# BOOST_CNTRL_CARD.net
KiCad netlist of a schematic drawn in Altium Designer
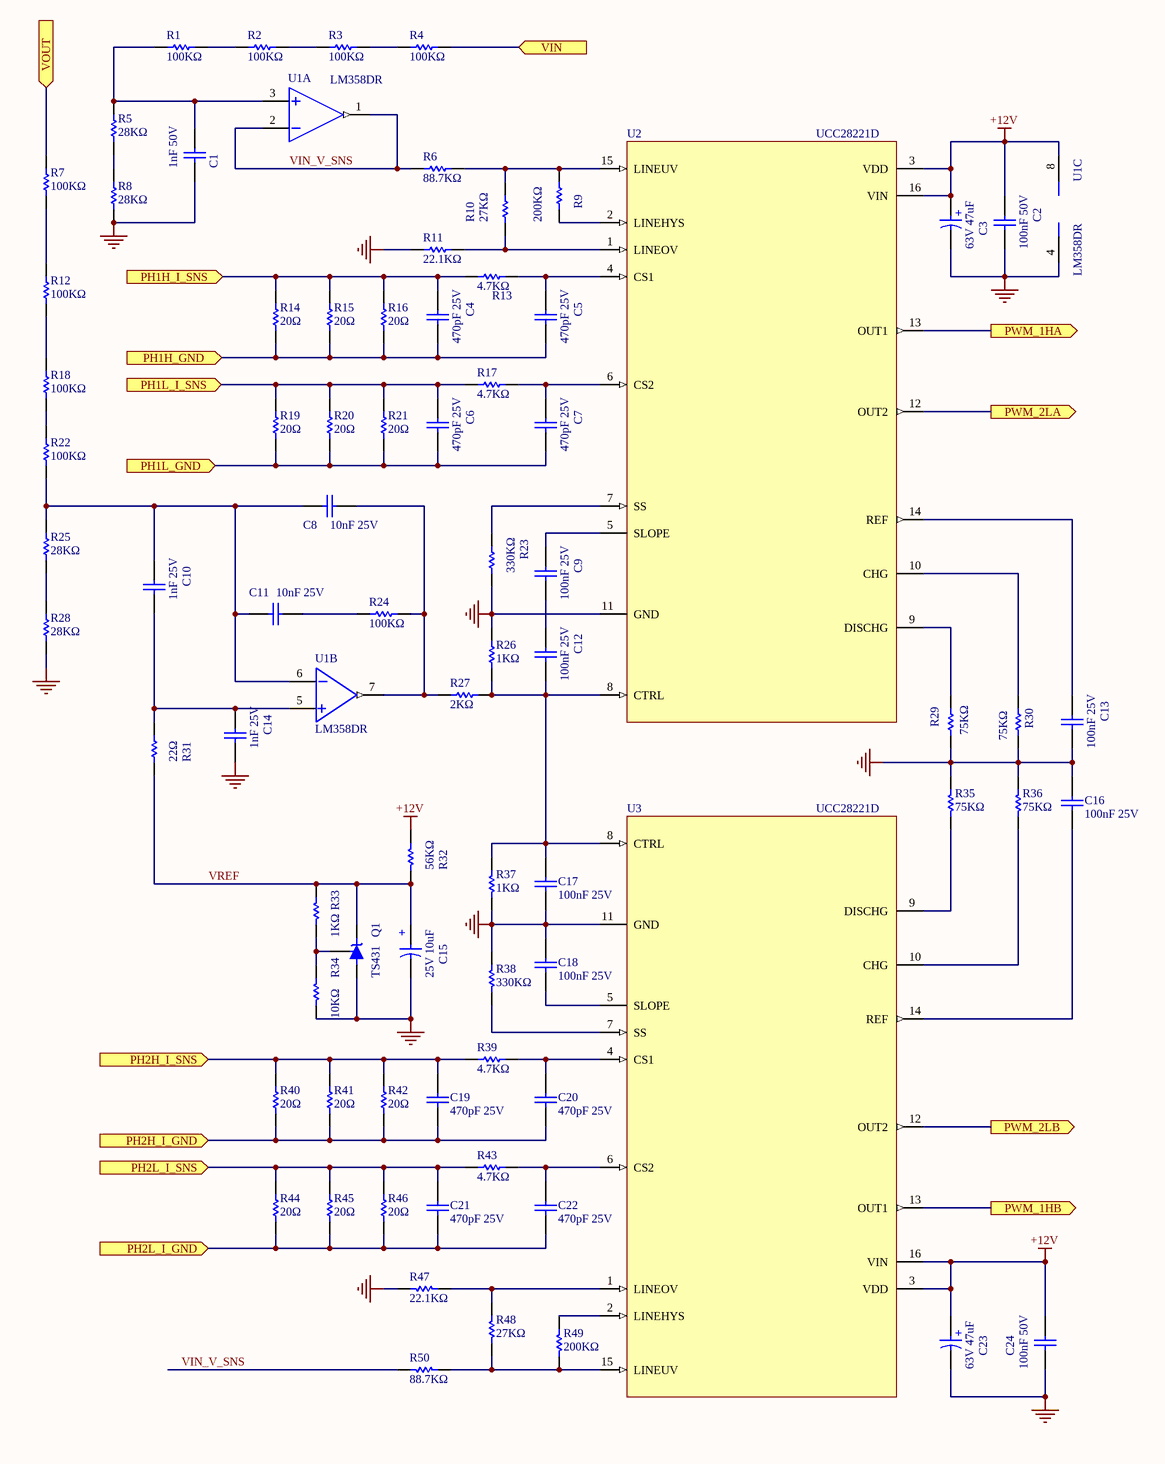
[diagram p0: BOOST CNTRL CARD.SchDoc]

(export (version "E")
  (design (tool "Eeschema 10.0.6"))
  (components
    (comp (ref "C1")
      (value "1nF 50V")
      (footprint "WCAP-CSGP_0402_L1W0.5H0.5")
      (description "WCAP-CSGP Multilayer Ceramic Chip Capacitor, General Purpose, size 0402, NP0, 1nF, 50VDC")
      (fields
        (field (name "MANUFACTURER PART NUMBER") "885012005067")
        (field (name "MANUFACTURER") "Wurth Elektronik")
      )
      (libsource (lib "WE - Passive Components") (part "Capacitor_Non-Polarized"))
    )
    (comp (ref "C2")
      (value "100nF 50V")
      (footprint "WCAP-CSGP_0805_L2W1.25H0.8_Reflow")
      (description "WCAP-CSGP Multilayer Ceramic Chip Capacitor, General Purpose, size 0805, X7R, 100nF, 50VDC")
      (fields
        (field (name "MANUFACTURER PART NUMBER") "885012207098")
        (field (name "MANUFACTURER") "Wurth Elektronik")
      )
      (libsource (lib "WE - Passive Components") (part "Capacitor_Non-Polarized"))
    )
    (comp (ref "C3")
      (value "63V 47uF")
      (footprint "WCAP-ASLI_D8H10.5")
      (description "WCAP-ASLI Aluminum Electrolytic Capacitor, V-Chip, D8 x H10.5mm, 47uF, 63V")
      (fields
        (field (name "MANUFACTURER PART NUMBER") "865080753013")
        (field (name "MANUFACTURER") "Wurth Elektronik")
      )
      (libsource (lib "WE - Passive Components") (part "Capacitor_Polarized"))
    )
    (comp (ref "C4")
      (value "470pF 25V")
      (footprint "WCAP-CSGP_0402_L1W0.5H0.5")
      (description "WCAP-CSGP Multilayer Ceramic Chip Capacitor, General Purpose, size 0402, X7R, 470pF, 25VDC")
      (fields
        (field (name "MANUFACTURER PART NUMBER") "885012205042")
        (field (name "MANUFACTURER") "Wurth Elektronik")
      )
      (libsource (lib "WE - Passive Components") (part "Capacitor_Non-Polarized"))
    )
    (comp (ref "C5")
      (value "470pF 25V")
      (footprint "WCAP-CSGP_0402_L1W0.5H0.5")
      (description "WCAP-CSGP Multilayer Ceramic Chip Capacitor, General Purpose, size 0402, X7R, 470pF, 25VDC")
      (fields
        (field (name "MANUFACTURER PART NUMBER") "885012205042")
        (field (name "MANUFACTURER") "Wurth Elektronik")
      )
      (libsource (lib "WE - Passive Components") (part "Capacitor_Non-Polarized"))
    )
    (comp (ref "C6")
      (value "470pF 25V")
      (footprint "WCAP-CSGP_0402_L1W0.5H0.5")
      (description "WCAP-CSGP Multilayer Ceramic Chip Capacitor, General Purpose, size 0402, X7R, 470pF, 25VDC")
      (fields
        (field (name "MANUFACTURER PART NUMBER") "885012205042")
        (field (name "MANUFACTURER") "Wurth Elektronik")
      )
      (libsource (lib "WE - Passive Components") (part "Capacitor_Non-Polarized"))
    )
    (comp (ref "C7")
      (value "470pF 25V")
      (footprint "WCAP-CSGP_0402_L1W0.5H0.5")
      (description "WCAP-CSGP Multilayer Ceramic Chip Capacitor, General Purpose, size 0402, X7R, 470pF, 25VDC")
      (fields
        (field (name "MANUFACTURER PART NUMBER") "885012205042")
        (field (name "MANUFACTURER") "Wurth Elektronik")
      )
      (libsource (lib "WE - Passive Components") (part "Capacitor_Non-Polarized"))
    )
    (comp (ref "C8")
      (value "10nF 25V")
      (footprint "WCAP-CSGP_0201_L0.6W0.3H0.3")
      (description "WCAP-CSGP Multilayer Ceramic Chip Capacitor, General Purpose, size 0201, X7R Class II, 10nF, 25VDC")
      (fields
        (field (name "MANUFACTURER PART NUMBER") "885012204004")
        (field (name "MANUFACTURER") "Wurth Elektronik")
      )
      (libsource (lib "WE - Passive Components") (part "Capacitor_Non-Polarized"))
    )
    (comp (ref "C9")
      (value "100nF 25V")
      (footprint "WCAP-CSGP_0402_L1W0.5H0.5")
      (description "WCAP-CSGP Multilayer Ceramic Chip Capacitor, General Purpose, size 0402, X7R, 100nF, 25VDC")
      (fields
        (field (name "MANUFACTURER PART NUMBER") "885012205085R")
        (field (name "MANUFACTURER") "Wurth Elektronik")
      )
      (libsource (lib "WE - Passive Components") (part "Capacitor_Non-Polarized"))
    )
    (comp (ref "C10")
      (value "1nF 25V")
      (footprint "WCAP-CSGP_0201_L0.6W0.3H0.3")
      (description "WCAP-CSGP Multilayer Ceramic Chip Capacitor, General Purpose, size 0201, X7R Class II, 1nF, 25VDC")
      (fields
        (field (name "MANUFACTURER PART NUMBER") "885012204006")
        (field (name "MANUFACTURER") "Wurth Elektronik")
      )
      (libsource (lib "WE - Passive Components") (part "Capacitor_Non-Polarized"))
    )
    (comp (ref "C11")
      (value "10nF 25V")
      (footprint "WCAP-CSGP_0201_L0.6W0.3H0.3")
      (description "WCAP-CSGP Multilayer Ceramic Chip Capacitor, General Purpose, size 0201, X7R Class II, 10nF, 25VDC")
      (fields
        (field (name "MANUFACTURER PART NUMBER") "885012204004")
        (field (name "MANUFACTURER") "Wurth Elektronik")
      )
      (libsource (lib "WE - Passive Components") (part "Capacitor_Non-Polarized"))
    )
    (comp (ref "C12")
      (value "100nF 25V")
      (footprint "WCAP-CSGP_0402_L1W0.5H0.5")
      (description "WCAP-CSGP Multilayer Ceramic Chip Capacitor, General Purpose, size 0402, X7R, 100nF, 25VDC")
      (fields
        (field (name "MANUFACTURER PART NUMBER") "885012205085R")
        (field (name "MANUFACTURER") "Wurth Elektronik")
      )
      (libsource (lib "WE - Passive Components") (part "Capacitor_Non-Polarized"))
    )
    (comp (ref "C13")
      (value "100nF 25V")
      (footprint "WCAP-CSGP_0402_L1W0.5H0.5")
      (description "WCAP-CSGP Multilayer Ceramic Chip Capacitor, General Purpose, size 0402, X7R, 100nF, 25VDC")
      (fields
        (field (name "MANUFACTURER PART NUMBER") "885012205085R")
        (field (name "MANUFACTURER") "Wurth Elektronik")
      )
      (libsource (lib "WE - Passive Components") (part "Capacitor_Non-Polarized"))
    )
    (comp (ref "C14")
      (value "1nF 25V")
      (footprint "WCAP-CSGP_0201_L0.6W0.3H0.3")
      (description "WCAP-CSGP Multilayer Ceramic Chip Capacitor, General Purpose, size 0201, X7R Class II, 1nF, 25VDC")
      (fields
        (field (name "MANUFACTURER PART NUMBER") "885012204006")
        (field (name "MANUFACTURER") "Wurth Elektronik")
      )
      (libsource (lib "WE - Passive Components") (part "Capacitor_Non-Polarized"))
    )
    (comp (ref "C15")
      (value "25V 10uF")
      (footprint "WCAP-AS5H_D4H5.5")
      (description "WCAP-AS5H Aluminum Electrolytic Capacitor, V-Chip, D4 x H5.5mm, 10µF, 25V")
      (fields
        (field (name "MANUFACTURER PART NUMBER") "865230440002")
        (field (name "MANUFACTURER") "Wurth Elektronik")
      )
      (libsource (lib "") (part "Capacitor_Polarized_1"))
    )
    (comp (ref "C16")
      (value "100nF 25V")
      (footprint "WCAP-CSGP_0402_L1W0.5H0.5")
      (description "WCAP-CSGP Multilayer Ceramic Chip Capacitor, General Purpose, size 0402, X7R, 100nF, 25VDC")
      (fields
        (field (name "MANUFACTURER PART NUMBER") "885012205085R")
        (field (name "MANUFACTURER") "Wurth Elektronik")
      )
      (libsource (lib "WE - Passive Components") (part "Capacitor_Non-Polarized"))
    )
    (comp (ref "C17")
      (value "100nF 25V")
      (footprint "WCAP-CSGP_0402_L1W0.5H0.5")
      (description "WCAP-CSGP Multilayer Ceramic Chip Capacitor, General Purpose, size 0402, X7R, 100nF, 25VDC")
      (fields
        (field (name "MANUFACTURER PART NUMBER") "885012205085R")
        (field (name "MANUFACTURER") "Wurth Elektronik")
      )
      (libsource (lib "WE - Passive Components") (part "Capacitor_Non-Polarized"))
    )
    (comp (ref "C18")
      (value "100nF 25V")
      (footprint "WCAP-CSGP_0402_L1W0.5H0.5")
      (description "WCAP-CSGP Multilayer Ceramic Chip Capacitor, General Purpose, size 0402, X7R, 100nF, 25VDC")
      (fields
        (field (name "MANUFACTURER PART NUMBER") "885012205085R")
        (field (name "MANUFACTURER") "Wurth Elektronik")
      )
      (libsource (lib "WE - Passive Components") (part "Capacitor_Non-Polarized"))
    )
    (comp (ref "C19")
      (value "470pF 25V")
      (footprint "WCAP-CSGP_0402_L1W0.5H0.5")
      (description "WCAP-CSGP Multilayer Ceramic Chip Capacitor, General Purpose, size 0402, X7R, 470pF, 25VDC")
      (fields
        (field (name "MANUFACTURER PART NUMBER") "885012205042")
        (field (name "MANUFACTURER") "Wurth Elektronik")
      )
      (libsource (lib "WE - Passive Components") (part "Capacitor_Non-Polarized"))
    )
    (comp (ref "C20")
      (value "470pF 25V")
      (footprint "WCAP-CSGP_0402_L1W0.5H0.5")
      (description "WCAP-CSGP Multilayer Ceramic Chip Capacitor, General Purpose, size 0402, X7R, 470pF, 25VDC")
      (fields
        (field (name "MANUFACTURER PART NUMBER") "885012205042")
        (field (name "MANUFACTURER") "Wurth Elektronik")
      )
      (libsource (lib "WE - Passive Components") (part "Capacitor_Non-Polarized"))
    )
    (comp (ref "C21")
      (value "470pF 25V")
      (footprint "WCAP-CSGP_0402_L1W0.5H0.5")
      (description "WCAP-CSGP Multilayer Ceramic Chip Capacitor, General Purpose, size 0402, X7R, 470pF, 25VDC")
      (fields
        (field (name "MANUFACTURER PART NUMBER") "885012205042")
        (field (name "MANUFACTURER") "Wurth Elektronik")
      )
      (libsource (lib "WE - Passive Components") (part "Capacitor_Non-Polarized"))
    )
    (comp (ref "C22")
      (value "470pF 25V")
      (footprint "WCAP-CSGP_0402_L1W0.5H0.5")
      (description "WCAP-CSGP Multilayer Ceramic Chip Capacitor, General Purpose, size 0402, X7R, 470pF, 25VDC")
      (fields
        (field (name "MANUFACTURER PART NUMBER") "885012205042")
        (field (name "MANUFACTURER") "Wurth Elektronik")
      )
      (libsource (lib "WE - Passive Components") (part "Capacitor_Non-Polarized"))
    )
    (comp (ref "C23")
      (value "63V 47uF")
      (footprint "WCAP-ASLI_D8H10.5")
      (description "WCAP-ASLI Aluminum Electrolytic Capacitor, V-Chip, D8 x H10.5mm, 47uF, 63V")
      (fields
        (field (name "MANUFACTURER PART NUMBER") "865080753013")
        (field (name "MANUFACTURER") "Wurth Elektronik")
      )
      (libsource (lib "WE - Passive Components") (part "Capacitor_Polarized"))
    )
    (comp (ref "C24")
      (value "100nF 50V")
      (footprint "WCAP-CSGP_0805_L2W1.25H0.8_Reflow")
      (description "WCAP-CSGP Multilayer Ceramic Chip Capacitor, General Purpose, size 0805, X7R, 100nF, 50VDC")
      (fields
        (field (name "MANUFACTURER PART NUMBER") "885012207098")
        (field (name "MANUFACTURER") "Wurth Elektronik")
      )
      (libsource (lib "WE - Passive Components") (part "Capacitor_Non-Polarized"))
    )
    (comp (ref "Q1")
      (value "TS431")
      (footprint "TO-92")
      (description "V-Ref Adjustable 1.24V to 6V 30mA 3-Pin TO-92 T/R")
      (fields
        (field (name "MANUFACTURER") "STMicroelectronics")
        (field (name "MANUFACTURER PART NUMBER") "TS431IZT")
      )
      (libsource (lib "Power Devices") (part "TS431IZT"))
    )
    (comp (ref "R1")
      (value "100KΩ")
      (footprint "WRIS-RSKS_0402")
      (description "WRIS-RSKS Thick Film Resistor, size 0402, 100000Ohm, 100mW")
      (fields
        (field (name "MANUFACTURER PART NUMBER") "560112110019")
        (field (name "MANUFACTURER") "Wurth Elektronik")
      )
      (libsource (lib "WE - Passive Components") (part "WRIS-RSKS"))
    )
    (comp (ref "R2")
      (value "100KΩ")
      (footprint "WRIS-RSKS_0402")
      (description "WRIS-RSKS Thick Film Resistor, size 0402, 100000Ohm, 100mW")
      (fields
        (field (name "MANUFACTURER PART NUMBER") "560112110019")
        (field (name "MANUFACTURER") "Wurth Elektronik")
      )
      (libsource (lib "WE - Passive Components") (part "WRIS-RSKS"))
    )
    (comp (ref "R3")
      (value "100KΩ")
      (footprint "WRIS-RSKS_0402")
      (description "WRIS-RSKS Thick Film Resistor, size 0402, 100000Ohm, 100mW")
      (fields
        (field (name "MANUFACTURER PART NUMBER") "560112110019")
        (field (name "MANUFACTURER") "Wurth Elektronik")
      )
      (libsource (lib "WE - Passive Components") (part "WRIS-RSKS"))
    )
    (comp (ref "R4")
      (value "100KΩ")
      (footprint "WRIS-RSKS_0402")
      (description "WRIS-RSKS Thick Film Resistor, size 0402, 100000Ohm, 100mW")
      (fields
        (field (name "MANUFACTURER PART NUMBER") "560112110019")
        (field (name "MANUFACTURER") "Wurth Elektronik")
      )
      (libsource (lib "WE - Passive Components") (part "WRIS-RSKS"))
    )
    (comp (ref "R5")
      (value "28KΩ")
      (footprint "WRIS-RSKS_0402")
      (description "WRIS-RSKS Thick Film Resistor, size 0402, 28000Ohm, 100mW")
      (fields
        (field (name "MANUFACTURER PART NUMBER") "560112110228")
        (field (name "MANUFACTURER") "Wurth Elektronik")
      )
      (libsource (lib "WE - Passive Components") (part "WRIS-RSKS"))
    )
    (comp (ref "R6")
      (value "88.7KΩ")
      (footprint "WRIS-RSKS_0402")
      (description "WRIS-RSKS Thick Film Resistor, size 0402, 88700Ohm, 100mW")
      (fields
        (field (name "MANUFACTURER PART NUMBER") "560112110139")
        (field (name "MANUFACTURER") "Wurth Elektronik")
      )
      (libsource (lib "WE - Passive Components") (part "WRIS-RSKS"))
    )
    (comp (ref "R7")
      (value "100KΩ")
      (footprint "WRIS-RSKS_0402")
      (description "WRIS-RSKS Thick Film Resistor, size 0402, 100000Ohm, 100mW")
      (fields
        (field (name "MANUFACTURER PART NUMBER") "560112110019")
        (field (name "MANUFACTURER") "Wurth Elektronik")
      )
      (libsource (lib "WE - Passive Components") (part "WRIS-RSKS"))
    )
    (comp (ref "R8")
      (value "28KΩ")
      (footprint "WRIS-RSKS_0402")
      (description "WRIS-RSKS Thick Film Resistor, size 0402, 28000Ohm, 100mW")
      (fields
        (field (name "MANUFACTURER PART NUMBER") "560112110228")
        (field (name "MANUFACTURER") "Wurth Elektronik")
      )
      (libsource (lib "WE - Passive Components") (part "WRIS-RSKS"))
    )
    (comp (ref "R9")
      (value "200KΩ")
      (footprint "WRIS-RSKS_0402")
      (description "WRIS-RSKS Thick Film Resistor, size 0402, 200000Ohm, 100mW")
      (fields
        (field (name "MANUFACTURER PART NUMBER") "560112110041")
        (field (name "MANUFACTURER") "Wurth Elektronik")
      )
      (libsource (lib "WE - Passive Components") (part "WRIS-RSKS"))
    )
    (comp (ref "R10")
      (value "27KΩ")
      (footprint "WRIS-RSKS_0402")
      (description "WRIS-RSKS Thick Film Resistor, size 0402, 27000Ohm, 100mW")
      (fields
        (field (name "MANUFACTURER PART NUMBER") "560112110026")
        (field (name "MANUFACTURER") "Wurth Elektronik")
      )
      (libsource (lib "WE - Passive Components") (part "WRIS-RSKS"))
    )
    (comp (ref "R11")
      (value "22.1KΩ")
      (footprint "WRIS-RSKS_0402")
      (description "WRIS-RSKS Thick Film Resistor, size 0402, 22100Ohm, 100mW")
      (fields
        (field (name "MANUFACTURER PART NUMBER") "560112110099")
        (field (name "MANUFACTURER") "Wurth Elektronik")
      )
      (libsource (lib "WE - Passive Components") (part "WRIS-RSKS"))
    )
    (comp (ref "R12")
      (value "100KΩ")
      (footprint "WRIS-RSKS_0402")
      (description "WRIS-RSKS Thick Film Resistor, size 0402, 100000Ohm, 100mW")
      (fields
        (field (name "MANUFACTURER PART NUMBER") "560112110019")
        (field (name "MANUFACTURER") "Wurth Elektronik")
      )
      (libsource (lib "WE - Passive Components") (part "WRIS-RSKS"))
    )
    (comp (ref "R13")
      (value "4.7KΩ")
      (footprint "WRIS-RSKS_0402")
      (description "WRIS-RSKS Thick Film Resistor, size 0402, 4700Ohm, 100mW")
      (fields
        (field (name "MANUFACTURER PART NUMBER") "560112110018")
        (field (name "MANUFACTURER") "Wurth Elektronik")
      )
      (libsource (lib "WE - Passive Components") (part "WRIS-RSKS"))
    )
    (comp (ref "R14")
      (value "20Ω")
      (footprint "WRIS-RSKS_0402")
      (description "WRIS-RSKS Thick Film Resistor, size 0402, 20Ohm, 100mW")
      (fields
        (field (name "MANUFACTURER PART NUMBER") "560112110083")
        (field (name "MANUFACTURER") "Wurth Elektronik")
      )
      (libsource (lib "WE - Passive Components") (part "WRIS-RSKS"))
    )
    (comp (ref "R15")
      (value "20Ω")
      (footprint "WRIS-RSKS_0402")
      (description "WRIS-RSKS Thick Film Resistor, size 0402, 20Ohm, 100mW")
      (fields
        (field (name "MANUFACTURER PART NUMBER") "560112110083")
        (field (name "MANUFACTURER") "Wurth Elektronik")
      )
      (libsource (lib "WE - Passive Components") (part "WRIS-RSKS"))
    )
    (comp (ref "R16")
      (value "20Ω")
      (footprint "WRIS-RSKS_0402")
      (description "WRIS-RSKS Thick Film Resistor, size 0402, 20Ohm, 100mW")
      (fields
        (field (name "MANUFACTURER PART NUMBER") "560112110083")
        (field (name "MANUFACTURER") "Wurth Elektronik")
      )
      (libsource (lib "WE - Passive Components") (part "WRIS-RSKS"))
    )
    (comp (ref "R17")
      (value "4.7KΩ")
      (footprint "WRIS-RSKS_0402")
      (description "WRIS-RSKS Thick Film Resistor, size 0402, 4700Ohm, 100mW")
      (fields
        (field (name "MANUFACTURER PART NUMBER") "560112110018")
        (field (name "MANUFACTURER") "Wurth Elektronik")
      )
      (libsource (lib "WE - Passive Components") (part "WRIS-RSKS"))
    )
    (comp (ref "R18")
      (value "100KΩ")
      (footprint "WRIS-RSKS_0402")
      (description "WRIS-RSKS Thick Film Resistor, size 0402, 100000Ohm, 100mW")
      (fields
        (field (name "MANUFACTURER PART NUMBER") "560112110019")
        (field (name "MANUFACTURER") "Wurth Elektronik")
      )
      (libsource (lib "WE - Passive Components") (part "WRIS-RSKS"))
    )
    (comp (ref "R19")
      (value "20Ω")
      (footprint "WRIS-RSKS_0402")
      (description "WRIS-RSKS Thick Film Resistor, size 0402, 20Ohm, 100mW")
      (fields
        (field (name "MANUFACTURER PART NUMBER") "560112110083")
        (field (name "MANUFACTURER") "Wurth Elektronik")
      )
      (libsource (lib "WE - Passive Components") (part "WRIS-RSKS"))
    )
    (comp (ref "R20")
      (value "20Ω")
      (footprint "WRIS-RSKS_0402")
      (description "WRIS-RSKS Thick Film Resistor, size 0402, 20Ohm, 100mW")
      (fields
        (field (name "MANUFACTURER PART NUMBER") "560112110083")
        (field (name "MANUFACTURER") "Wurth Elektronik")
      )
      (libsource (lib "WE - Passive Components") (part "WRIS-RSKS"))
    )
    (comp (ref "R21")
      (value "20Ω")
      (footprint "WRIS-RSKS_0402")
      (description "WRIS-RSKS Thick Film Resistor, size 0402, 20Ohm, 100mW")
      (fields
        (field (name "MANUFACTURER PART NUMBER") "560112110083")
        (field (name "MANUFACTURER") "Wurth Elektronik")
      )
      (libsource (lib "WE - Passive Components") (part "WRIS-RSKS"))
    )
    (comp (ref "R22")
      (value "100KΩ")
      (footprint "WRIS-RSKS_0402")
      (description "WRIS-RSKS Thick Film Resistor, size 0402, 100000Ohm, 100mW")
      (fields
        (field (name "MANUFACTURER PART NUMBER") "560112110019")
        (field (name "MANUFACTURER") "Wurth Elektronik")
      )
      (libsource (lib "WE - Passive Components") (part "WRIS-RSKS"))
    )
    (comp (ref "R23")
      (value "330KΩ")
      (footprint "WRIS-RSKS_0402")
      (description "WRIS-RSKS Thick Film Resistor, size 0402, 330000Ohm, 100mW")
      (fields
        (field (name "MANUFACTURER PART NUMBER") "560112110088")
        (field (name "MANUFACTURER") "Wurth Elektronik")
      )
      (libsource (lib "WE - Passive Components") (part "WRIS-RSKS"))
    )
    (comp (ref "R24")
      (value "100KΩ")
      (footprint "WRIS-RSKS_0402")
      (description "WRIS-RSKS Thick Film Resistor, size 0402, 100000Ohm, 100mW")
      (fields
        (field (name "MANUFACTURER PART NUMBER") "560112110019")
        (field (name "MANUFACTURER") "Wurth Elektronik")
      )
      (libsource (lib "WE - Passive Components") (part "WRIS-RSKS"))
    )
    (comp (ref "R25")
      (value "28KΩ")
      (footprint "WRIS-RSKS_0402")
      (description "WRIS-RSKS Thick Film Resistor, size 0402, 28000Ohm, 100mW")
      (fields
        (field (name "MANUFACTURER PART NUMBER") "560112110228")
        (field (name "MANUFACTURER") "Wurth Elektronik")
      )
      (libsource (lib "WE - Passive Components") (part "WRIS-RSKS"))
    )
    (comp (ref "R26")
      (value "1KΩ")
      (footprint "WRIS-RSKS_0402")
      (description "WRIS-RSKS Thick Film Resistor, size 0402, 1000Ohm, 100mW")
      (fields
        (field (name "MANUFACTURER PART NUMBER") "560112110012")
        (field (name "MANUFACTURER") "Wurth Elektronik")
      )
      (libsource (lib "WE - Passive Components") (part "WRIS-RSKS"))
    )
    (comp (ref "R27")
      (value "2KΩ")
      (footprint "WRIS-RSKS_0402")
      (description "WRIS-RSKS Thick Film Resistor, size 0402, 2000Ohm, 100mW")
      (fields
        (field (name "MANUFACTURER PART NUMBER") "560112110064")
        (field (name "MANUFACTURER") "Wurth Elektronik")
      )
      (libsource (lib "WE - Passive Components") (part "WRIS-RSKS"))
    )
    (comp (ref "R28")
      (value "28KΩ")
      (footprint "WRIS-RSKS_0402")
      (description "WRIS-RSKS Thick Film Resistor, size 0402, 28000Ohm, 100mW")
      (fields
        (field (name "MANUFACTURER PART NUMBER") "560112110228")
        (field (name "MANUFACTURER") "Wurth Elektronik")
      )
      (libsource (lib "WE - Passive Components") (part "WRIS-RSKS"))
    )
    (comp (ref "R29")
      (value "75KΩ")
      (footprint "WRIS-RSKS_0603_Reflow")
      (description "WRIS-RSKS Thick Film Resistor, size 0603, 75000Ohm, 100mW")
      (fields
        (field (name "MANUFACTURER PART NUMBER") "560112116063")
        (field (name "MANUFACTURER") "Wurth Elektronik")
      )
      (libsource (lib "WE - Passive Components") (part "WRIS-RSKS"))
    )
    (comp (ref "R30")
      (value "75KΩ")
      (footprint "WRIS-RSKS_0603_Reflow")
      (description "WRIS-RSKS Thick Film Resistor, size 0603, 75000Ohm, 100mW")
      (fields
        (field (name "MANUFACTURER PART NUMBER") "560112116063")
        (field (name "MANUFACTURER") "Wurth Elektronik")
      )
      (libsource (lib "WE - Passive Components") (part "WRIS-RSKS"))
    )
    (comp (ref "R31")
      (value "22Ω")
      (footprint "WRIS-RSKS_0402")
      (description "WRIS-RSKS Thick Film Resistor, size 0402, 22Ohm, 100mW")
      (fields
        (field (name "MANUFACTURER PART NUMBER") "560112110046")
        (field (name "MANUFACTURER") "Wurth Elektronik")
      )
      (libsource (lib "WE - Passive Components") (part "WRIS-RSKS"))
    )
    (comp (ref "R32")
      (value "56KΩ")
      (footprint "WRIS-RSKS_0402")
      (description "WRIS-RSKS Thick Film Resistor, size 0402, 56000Ohm, 100mW")
      (fields
        (field (name "MANUFACTURER PART NUMBER") "560112110031")
        (field (name "MANUFACTURER") "Wurth Elektronik")
      )
      (libsource (lib "WE - Passive Components") (part "WRIS-RSKS"))
    )
    (comp (ref "R33")
      (value "1KΩ")
      (footprint "WRIS-RSKS_0402")
      (description "WRIS-RSKS Thick Film Resistor, size 0402, 1000Ohm, 100mW")
      (fields
        (field (name "MANUFACTURER PART NUMBER") "560112110012")
        (field (name "MANUFACTURER") "Wurth Elektronik")
      )
      (libsource (lib "WE - Passive Components") (part "WRIS-RSKS"))
    )
    (comp (ref "R34")
      (value "10KΩ")
      (footprint "WRIS-RSKS_0402")
      (description "WRIS-RSKS Thick Film Resistor, size 0402, 10000Ohm, 100mW")
      (fields
        (field (name "MANUFACTURER PART NUMBER") "560112110006")
        (field (name "MANUFACTURER") "Wurth Elektronik")
      )
      (libsource (lib "WE - Passive Components") (part "WRIS-RSKS"))
    )
    (comp (ref "R35")
      (value "75KΩ")
      (footprint "WRIS-RSKS_0603_Reflow")
      (description "WRIS-RSKS Thick Film Resistor, size 0603, 75000Ohm, 100mW")
      (fields
        (field (name "MANUFACTURER PART NUMBER") "560112116063")
        (field (name "MANUFACTURER") "Wurth Elektronik")
      )
      (libsource (lib "WE - Passive Components") (part "WRIS-RSKS"))
    )
    (comp (ref "R36")
      (value "75KΩ")
      (footprint "WRIS-RSKS_0603_Reflow")
      (description "WRIS-RSKS Thick Film Resistor, size 0603, 75000Ohm, 100mW")
      (fields
        (field (name "MANUFACTURER PART NUMBER") "560112116063")
        (field (name "MANUFACTURER") "Wurth Elektronik")
      )
      (libsource (lib "WE - Passive Components") (part "WRIS-RSKS"))
    )
    (comp (ref "R37")
      (value "1KΩ")
      (footprint "WRIS-RSKS_0402")
      (description "WRIS-RSKS Thick Film Resistor, size 0402, 1000Ohm, 100mW")
      (fields
        (field (name "MANUFACTURER PART NUMBER") "560112110012")
        (field (name "MANUFACTURER") "Wurth Elektronik")
      )
      (libsource (lib "WE - Passive Components") (part "WRIS-RSKS"))
    )
    (comp (ref "R38")
      (value "330KΩ")
      (footprint "WRIS-RSKS_0402")
      (description "WRIS-RSKS Thick Film Resistor, size 0402, 330000Ohm, 100mW")
      (fields
        (field (name "MANUFACTURER PART NUMBER") "560112110088")
        (field (name "MANUFACTURER") "Wurth Elektronik")
      )
      (libsource (lib "WE - Passive Components") (part "WRIS-RSKS"))
    )
    (comp (ref "R39")
      (value "4.7KΩ")
      (footprint "WRIS-RSKS_0402")
      (description "WRIS-RSKS Thick Film Resistor, size 0402, 4700Ohm, 100mW")
      (fields
        (field (name "MANUFACTURER PART NUMBER") "560112110018")
        (field (name "MANUFACTURER") "Wurth Elektronik")
      )
      (libsource (lib "WE - Passive Components") (part "WRIS-RSKS"))
    )
    (comp (ref "R40")
      (value "20Ω")
      (footprint "WRIS-RSKS_0402")
      (description "WRIS-RSKS Thick Film Resistor, size 0402, 20Ohm, 100mW")
      (fields
        (field (name "MANUFACTURER PART NUMBER") "560112110083")
        (field (name "MANUFACTURER") "Wurth Elektronik")
      )
      (libsource (lib "WE - Passive Components") (part "WRIS-RSKS"))
    )
    (comp (ref "R41")
      (value "20Ω")
      (footprint "WRIS-RSKS_0402")
      (description "WRIS-RSKS Thick Film Resistor, size 0402, 20Ohm, 100mW")
      (fields
        (field (name "MANUFACTURER PART NUMBER") "560112110083")
        (field (name "MANUFACTURER") "Wurth Elektronik")
      )
      (libsource (lib "WE - Passive Components") (part "WRIS-RSKS"))
    )
    (comp (ref "R42")
      (value "20Ω")
      (footprint "WRIS-RSKS_0402")
      (description "WRIS-RSKS Thick Film Resistor, size 0402, 20Ohm, 100mW")
      (fields
        (field (name "MANUFACTURER PART NUMBER") "560112110083")
        (field (name "MANUFACTURER") "Wurth Elektronik")
      )
      (libsource (lib "WE - Passive Components") (part "WRIS-RSKS"))
    )
    (comp (ref "R43")
      (value "4.7KΩ")
      (footprint "WRIS-RSKS_0402")
      (description "WRIS-RSKS Thick Film Resistor, size 0402, 4700Ohm, 100mW")
      (fields
        (field (name "MANUFACTURER PART NUMBER") "560112110018")
        (field (name "MANUFACTURER") "Wurth Elektronik")
      )
      (libsource (lib "WE - Passive Components") (part "WRIS-RSKS"))
    )
    (comp (ref "R44")
      (value "20Ω")
      (footprint "WRIS-RSKS_0402")
      (description "WRIS-RSKS Thick Film Resistor, size 0402, 20Ohm, 100mW")
      (fields
        (field (name "MANUFACTURER PART NUMBER") "560112110083")
        (field (name "MANUFACTURER") "Wurth Elektronik")
      )
      (libsource (lib "WE - Passive Components") (part "WRIS-RSKS"))
    )
    (comp (ref "R45")
      (value "20Ω")
      (footprint "WRIS-RSKS_0402")
      (description "WRIS-RSKS Thick Film Resistor, size 0402, 20Ohm, 100mW")
      (fields
        (field (name "MANUFACTURER PART NUMBER") "560112110083")
        (field (name "MANUFACTURER") "Wurth Elektronik")
      )
      (libsource (lib "WE - Passive Components") (part "WRIS-RSKS"))
    )
    (comp (ref "R46")
      (value "20Ω")
      (footprint "WRIS-RSKS_0402")
      (description "WRIS-RSKS Thick Film Resistor, size 0402, 20Ohm, 100mW")
      (fields
        (field (name "MANUFACTURER PART NUMBER") "560112110083")
        (field (name "MANUFACTURER") "Wurth Elektronik")
      )
      (libsource (lib "WE - Passive Components") (part "WRIS-RSKS"))
    )
    (comp (ref "R47")
      (value "22.1KΩ")
      (footprint "WRIS-RSKS_0402")
      (description "WRIS-RSKS Thick Film Resistor, size 0402, 22100Ohm, 100mW")
      (fields
        (field (name "MANUFACTURER PART NUMBER") "560112110099")
        (field (name "MANUFACTURER") "Wurth Elektronik")
      )
      (libsource (lib "WE - Passive Components") (part "WRIS-RSKS"))
    )
    (comp (ref "R48")
      (value "27KΩ")
      (footprint "WRIS-RSKS_0402")
      (description "WRIS-RSKS Thick Film Resistor, size 0402, 27000Ohm, 100mW")
      (fields
        (field (name "MANUFACTURER PART NUMBER") "560112110026")
        (field (name "MANUFACTURER") "Wurth Elektronik")
      )
      (libsource (lib "WE - Passive Components") (part "WRIS-RSKS"))
    )
    (comp (ref "R49")
      (value "200KΩ")
      (footprint "WRIS-RSKS_0402")
      (description "WRIS-RSKS Thick Film Resistor, size 0402, 200000Ohm, 100mW")
      (fields
        (field (name "MANUFACTURER PART NUMBER") "560112110041")
        (field (name "MANUFACTURER") "Wurth Elektronik")
      )
      (libsource (lib "WE - Passive Components") (part "WRIS-RSKS"))
    )
    (comp (ref "R50")
      (value "88.7KΩ")
      (footprint "WRIS-RSKS_0402")
      (description "WRIS-RSKS Thick Film Resistor, size 0402, 88700Ohm, 100mW")
      (fields
        (field (name "MANUFACTURER PART NUMBER") "560112110139")
        (field (name "MANUFACTURER") "Wurth Elektronik")
      )
      (libsource (lib "WE - Passive Components") (part "WRIS-RSKS"))
    )
    (comp (ref "U1")
      (value "LM358DR")
      (footprint "SOIC-08-IPC_A")
      (description "IC OPAMP GP 2 CIRCUIT 8SOIC")
      (libsource (lib "Integrated Circuits") (part "LM358 OPAMP"))
    )
    (comp (ref "U2")
      (value "UCC28221D")
      (footprint "D0016A_N")
      (fields (field (name "MANUFACTURER") "Texas Instruments"))
      (libsource (lib "") (part "UCC28221D_1"))
    )
    (comp (ref "U3")
      (value "UCC28221D")
      (footprint "D0016A_N")
      (fields (field (name "MANUFACTURER") "Texas Instruments"))
      (libsource (lib "Integrated Circuits") (part "UCC28221D"))
    )
  )
  (nets
    (net (code "1") (name "+12V") (class "Default")
      (node (ref "C2") (pin "2") (pinfunction "2_2") (pintype "passive"))
      (node (ref "C23") (pin "1") (pinfunction "P_1") (pintype "passive"))
      (node (ref "C24") (pin "2") (pinfunction "2_2") (pintype "passive"))
      (node (ref "C3") (pin "1") (pinfunction "P_1") (pintype "passive"))
      (node (ref "R32") (pin "2") (pinfunction "2_2") (pintype "passive"))
      (node (ref "U1") (pin "8") (pinfunction "V+_8") (pintype "power_in"))
      (node (ref "U2") (pin "16") (pinfunction "VIN_16") (pintype "power_in"))
      (node (ref "U2") (pin "3") (pinfunction "VDD_3") (pintype "power_in"))
      (node (ref "U3") (pin "16") (pinfunction "VIN_16") (pintype "power_in"))
      (node (ref "U3") (pin "3") (pinfunction "VDD_3") (pintype "power_in"))
    )
    (net (code "2") (name "/PH1H_GND") (class "Default")
      (node (ref "C4") (pin "1") (pinfunction "1_1") (pintype "passive"))
      (node (ref "C5") (pin "1") (pinfunction "1_1") (pintype "passive"))
      (node (ref "R14") (pin "1") (pinfunction "1_1") (pintype "passive"))
      (node (ref "R15") (pin "1") (pinfunction "1_1") (pintype "passive"))
      (node (ref "R16") (pin "1") (pinfunction "1_1") (pintype "passive"))
    )
    (net (code "3") (name "/PH1H_I_SNS") (class "Default")
      (node (ref "C4") (pin "2") (pinfunction "2_2") (pintype "passive"))
      (node (ref "R13") (pin "1") (pinfunction "1_1") (pintype "passive"))
      (node (ref "R14") (pin "2") (pinfunction "2_2") (pintype "passive"))
      (node (ref "R15") (pin "2") (pinfunction "2_2") (pintype "passive"))
      (node (ref "R16") (pin "2") (pinfunction "2_2") (pintype "passive"))
    )
    (net (code "4") (name "/PH1L_GND") (class "Default")
      (node (ref "C6") (pin "1") (pinfunction "1_1") (pintype "passive"))
      (node (ref "C7") (pin "1") (pinfunction "1_1") (pintype "passive"))
      (node (ref "R19") (pin "1") (pinfunction "1_1") (pintype "passive"))
      (node (ref "R20") (pin "1") (pinfunction "1_1") (pintype "passive"))
      (node (ref "R21") (pin "1") (pinfunction "1_1") (pintype "passive"))
    )
    (net (code "5") (name "/PH1L_I_SNS") (class "Default")
      (node (ref "C6") (pin "2") (pinfunction "2_2") (pintype "passive"))
      (node (ref "R17") (pin "1") (pinfunction "1_1") (pintype "passive"))
      (node (ref "R19") (pin "2") (pinfunction "2_2") (pintype "passive"))
      (node (ref "R20") (pin "2") (pinfunction "2_2") (pintype "passive"))
      (node (ref "R21") (pin "2") (pinfunction "2_2") (pintype "passive"))
    )
    (net (code "6") (name "/PH2H_I_GND") (class "Default")
      (node (ref "C19") (pin "1") (pinfunction "1_1") (pintype "passive"))
      (node (ref "C20") (pin "1") (pinfunction "1_1") (pintype "passive"))
      (node (ref "R40") (pin "1") (pinfunction "1_1") (pintype "passive"))
      (node (ref "R41") (pin "1") (pinfunction "1_1") (pintype "passive"))
      (node (ref "R42") (pin "1") (pinfunction "1_1") (pintype "passive"))
    )
    (net (code "7") (name "/PH2H_I_SNS") (class "Default")
      (node (ref "C19") (pin "2") (pinfunction "2_2") (pintype "passive"))
      (node (ref "R39") (pin "1") (pinfunction "1_1") (pintype "passive"))
      (node (ref "R40") (pin "2") (pinfunction "2_2") (pintype "passive"))
      (node (ref "R41") (pin "2") (pinfunction "2_2") (pintype "passive"))
      (node (ref "R42") (pin "2") (pinfunction "2_2") (pintype "passive"))
    )
    (net (code "8") (name "/PH2L_I_GND") (class "Default")
      (node (ref "C21") (pin "1") (pinfunction "1_1") (pintype "passive"))
      (node (ref "C22") (pin "1") (pinfunction "1_1") (pintype "passive"))
      (node (ref "R44") (pin "1") (pinfunction "1_1") (pintype "passive"))
      (node (ref "R45") (pin "1") (pinfunction "1_1") (pintype "passive"))
      (node (ref "R46") (pin "1") (pinfunction "1_1") (pintype "passive"))
    )
    (net (code "9") (name "/PH2L_I_SNS") (class "Default")
      (node (ref "C21") (pin "2") (pinfunction "2_2") (pintype "passive"))
      (node (ref "R43") (pin "1") (pinfunction "1_1") (pintype "passive"))
      (node (ref "R44") (pin "2") (pinfunction "2_2") (pintype "passive"))
      (node (ref "R45") (pin "2") (pinfunction "2_2") (pintype "passive"))
      (node (ref "R46") (pin "2") (pinfunction "2_2") (pintype "passive"))
    )
    (net (code "10") (name "/PWM_1HA") (class "Default")
      (node (ref "U2") (pin "13") (pinfunction "OUT1_13") (pintype "output"))
    )
    (net (code "11") (name "/PWM_1HB") (class "Default")
      (node (ref "U3") (pin "13") (pinfunction "OUT1_13") (pintype "output"))
    )
    (net (code "12") (name "/PWM_2LA") (class "Default")
      (node (ref "U2") (pin "12") (pinfunction "OUT2_12") (pintype "output"))
    )
    (net (code "13") (name "/PWM_2LB") (class "Default")
      (node (ref "U3") (pin "12") (pinfunction "OUT2_12") (pintype "output"))
    )
    (net (code "14") (name "/VIN") (class "Default")
      (node (ref "R4") (pin "2") (pinfunction "2_2") (pintype "passive"))
    )
    (net (code "15") (name "/VIN_V_SNS") (class "Default")
      (node (ref "R50") (pin "2") (pinfunction "2_2") (pintype "passive"))
      (node (ref "R6") (pin "2") (pinfunction "2_2") (pintype "passive"))
      (node (ref "U1") (pin "1") (pinfunction "1OUT_1") (pintype "output"))
      (node (ref "U1") (pin "2") (pinfunction "IN1-_2") (pintype "tri_state"))
    )
    (net (code "16") (name "/VOUT") (class "Default")
      (node (ref "R7") (pin "2") (pinfunction "2_2") (pintype "passive"))
    )
    (net (code "17") (name "/VREF") (class "Default")
      (node (ref "C15") (pin "1") (pinfunction "P_1") (pintype "passive"))
      (node (ref "Q1") (pin "1") (pinfunction "K_1") (pintype "passive"))
      (node (ref "R31") (pin "1") (pinfunction "1_1") (pintype "passive"))
      (node (ref "R32") (pin "1") (pinfunction "1_1") (pintype "passive"))
      (node (ref "R33") (pin "2") (pinfunction "2_2") (pintype "passive"))
    )
    (net (code "18") (name "GND") (class "Default")
      (node (ref "C1") (pin "1") (pinfunction "1_1") (pintype "passive"))
      (node (ref "C13") (pin "1") (pinfunction "1_1") (pintype "passive"))
      (node (ref "C14") (pin "1") (pinfunction "1_1") (pintype "passive"))
      (node (ref "C15") (pin "2") (pinfunction "N_2") (pintype "passive"))
      (node (ref "C16") (pin "1") (pinfunction "1_1") (pintype "passive"))
      (node (ref "C17") (pin "2") (pinfunction "2_2") (pintype "passive"))
      (node (ref "C18") (pin "1") (pinfunction "1_1") (pintype "passive"))
      (node (ref "C2") (pin "1") (pinfunction "1_1") (pintype "passive"))
      (node (ref "C23") (pin "2") (pinfunction "N_2") (pintype "passive"))
      (node (ref "C24") (pin "1") (pinfunction "1_1") (pintype "passive"))
      (node (ref "C3") (pin "2") (pinfunction "N_2") (pintype "passive"))
      (node (ref "Q1") (pin "1") (pinfunction "A_1") (pintype "passive"))
      (node (ref "R11") (pin "1") (pinfunction "1_1") (pintype "passive"))
      (node (ref "R23") (pin "1") (pinfunction "1_1") (pintype "passive"))
      (node (ref "R26") (pin "2") (pinfunction "2_2") (pintype "passive"))
      (node (ref "R28") (pin "1") (pinfunction "1_1") (pintype "passive"))
      (node (ref "R29") (pin "1") (pinfunction "1_1") (pintype "passive"))
      (node (ref "R30") (pin "1") (pinfunction "1_1") (pintype "passive"))
      (node (ref "R34") (pin "1") (pinfunction "1_1") (pintype "passive"))
      (node (ref "R35") (pin "1") (pinfunction "1_1") (pintype "passive"))
      (node (ref "R36") (pin "1") (pinfunction "1_1") (pintype "passive"))
      (node (ref "R37") (pin "2") (pinfunction "2_2") (pintype "passive"))
      (node (ref "R38") (pin "1") (pinfunction "1_1") (pintype "passive"))
      (node (ref "R47") (pin "1") (pinfunction "1_1") (pintype "passive"))
      (node (ref "R8") (pin "1") (pinfunction "1_1") (pintype "passive"))
      (node (ref "U1") (pin "4") (pinfunction "V-_4") (pintype "power_in"))
      (node (ref "U2") (pin "11") (pinfunction "GND_11") (pintype "power_in"))
      (node (ref "U3") (pin "11") (pinfunction "GND_11") (pintype "power_in"))
    )
    (net (code "19") (name "Net-(C11-Pad2)") (class "Default")
      (node (ref "C11") (pin "2") (pinfunction "2_2") (pintype "passive"))
      (node (ref "R24") (pin "1") (pinfunction "1_1") (pintype "passive"))
    )
    (net (code "20") (name "Net-(C12-Pad2)") (class "Default")
      (node (ref "C12") (pin "2") (pinfunction "2_2") (pintype "passive"))
      (node (ref "C9") (pin "1") (pinfunction "1_1") (pintype "passive"))
    )
    (net (code "21") (name "Net-(Q1-REF)") (class "Default")
      (node (ref "Q1") (pin "3") (pinfunction "REF_3") (pintype "passive"))
      (node (ref "R33") (pin "1") (pinfunction "1_1") (pintype "passive"))
      (node (ref "R34") (pin "2") (pinfunction "2_2") (pintype "passive"))
    )
    (net (code "22") (name "Net-(R1-Pad2)") (class "Default")
      (node (ref "R1") (pin "2") (pinfunction "2_2") (pintype "passive"))
      (node (ref "R2") (pin "1") (pinfunction "1_1") (pintype "passive"))
    )
    (net (code "23") (name "Net-(R2-Pad2)") (class "Default")
      (node (ref "R2") (pin "2") (pinfunction "2_2") (pintype "passive"))
      (node (ref "R3") (pin "1") (pinfunction "1_1") (pintype "passive"))
    )
    (net (code "24") (name "Net-(R3-Pad2)") (class "Default")
      (node (ref "R3") (pin "2") (pinfunction "2_2") (pintype "passive"))
      (node (ref "R4") (pin "1") (pinfunction "1_1") (pintype "passive"))
    )
    (net (code "25") (name "Net-(R5-Pad1)") (class "Default")
      (node (ref "R5") (pin "1") (pinfunction "1_1") (pintype "passive"))
      (node (ref "R8") (pin "2") (pinfunction "2_2") (pintype "passive"))
    )
    (net (code "26") (name "Net-(R12-Pad1)") (class "Default")
      (node (ref "R12") (pin "1") (pinfunction "1_1") (pintype "passive"))
      (node (ref "R18") (pin "2") (pinfunction "2_2") (pintype "passive"))
    )
    (net (code "27") (name "Net-(R12-Pad2)") (class "Default")
      (node (ref "R12") (pin "2") (pinfunction "2_2") (pintype "passive"))
      (node (ref "R7") (pin "1") (pinfunction "1_1") (pintype "passive"))
    )
    (net (code "28") (name "Net-(R18-Pad1)") (class "Default")
      (node (ref "R18") (pin "1") (pinfunction "1_1") (pintype "passive"))
      (node (ref "R22") (pin "2") (pinfunction "2_2") (pintype "passive"))
    )
    (net (code "29") (name "Net-(R25-Pad1)") (class "Default")
      (node (ref "R25") (pin "1") (pinfunction "1_1") (pintype "passive"))
      (node (ref "R28") (pin "2") (pinfunction "2_2") (pintype "passive"))
    )
    (net (code "30") (name "Net-(U1A-IN1+)") (class "Default")
      (node (ref "C1") (pin "2") (pinfunction "2_2") (pintype "passive"))
      (node (ref "R1") (pin "1") (pinfunction "1_1") (pintype "passive"))
      (node (ref "R5") (pin "2") (pinfunction "2_2") (pintype "passive"))
      (node (ref "U1") (pin "3") (pinfunction "IN1+_3") (pintype "tri_state"))
    )
    (net (code "31") (name "Net-(U1B-2OUT)") (class "Default")
      (node (ref "C8") (pin "2") (pinfunction "2_2") (pintype "passive"))
      (node (ref "R24") (pin "2") (pinfunction "2_2") (pintype "passive"))
      (node (ref "R27") (pin "1") (pinfunction "1_1") (pintype "passive"))
      (node (ref "U1") (pin "7") (pinfunction "2OUT_7") (pintype "output"))
    )
    (net (code "32") (name "Net-(U1B-IN2+)") (class "Default")
      (node (ref "C10") (pin "1") (pinfunction "1_1") (pintype "passive"))
      (node (ref "C14") (pin "2") (pinfunction "2_2") (pintype "passive"))
      (node (ref "R31") (pin "2") (pinfunction "2_2") (pintype "passive"))
      (node (ref "U1") (pin "5") (pinfunction "IN2+_5") (pintype "tri_state"))
    )
    (net (code "33") (name "Net-(U1B-IN2-)") (class "Default")
      (node (ref "C10") (pin "2") (pinfunction "2_2") (pintype "passive"))
      (node (ref "C11") (pin "1") (pinfunction "1_1") (pintype "passive"))
      (node (ref "C8") (pin "1") (pinfunction "1_1") (pintype "passive"))
      (node (ref "R22") (pin "1") (pinfunction "1_1") (pintype "passive"))
      (node (ref "R25") (pin "2") (pinfunction "2_2") (pintype "passive"))
      (node (ref "U1") (pin "6") (pinfunction "IN2-_6") (pintype "tri_state"))
    )
    (net (code "34") (name "Net-(U2-CHG)") (class "Default")
      (node (ref "R30") (pin "2") (pinfunction "2_2") (pintype "passive"))
      (node (ref "U2") (pin "10") (pinfunction "CHG_10") (pintype "passive"))
    )
    (net (code "35") (name "Net-(U2-CS1)") (class "Default")
      (node (ref "C5") (pin "2") (pinfunction "2_2") (pintype "passive"))
      (node (ref "R13") (pin "2") (pinfunction "2_2") (pintype "passive"))
      (node (ref "U2") (pin "4") (pinfunction "CS1_4") (pintype "input"))
    )
    (net (code "36") (name "Net-(U2-CS2)") (class "Default")
      (node (ref "C7") (pin "2") (pinfunction "2_2") (pintype "passive"))
      (node (ref "R17") (pin "2") (pinfunction "2_2") (pintype "passive"))
      (node (ref "U2") (pin "6") (pinfunction "CS2_6") (pintype "input"))
    )
    (net (code "37") (name "Net-(U2-CTRL)") (class "Default")
      (node (ref "C12") (pin "1") (pinfunction "1_1") (pintype "passive"))
      (node (ref "C17") (pin "1") (pinfunction "1_1") (pintype "passive"))
      (node (ref "R26") (pin "1") (pinfunction "1_1") (pintype "passive"))
      (node (ref "R27") (pin "2") (pinfunction "2_2") (pintype "passive"))
      (node (ref "R37") (pin "1") (pinfunction "1_1") (pintype "passive"))
      (node (ref "U2") (pin "8") (pinfunction "CTRL_8") (pintype "input"))
      (node (ref "U3") (pin "8") (pinfunction "CTRL_8") (pintype "input"))
    )
    (net (code "38") (name "Net-(U2-DISCHG)") (class "Default")
      (node (ref "R29") (pin "2") (pinfunction "2_2") (pintype "passive"))
      (node (ref "U2") (pin "9") (pinfunction "DISCHG_9") (pintype "passive"))
    )
    (net (code "39") (name "Net-(U2-LINEHYS)") (class "Default")
      (node (ref "R9") (pin "1") (pinfunction "1_1") (pintype "passive"))
      (node (ref "U2") (pin "2") (pinfunction "LINEHYS_2") (pintype "input"))
    )
    (net (code "40") (name "Net-(U2-LINEOV)") (class "Default")
      (node (ref "R10") (pin "1") (pinfunction "1_1") (pintype "passive"))
      (node (ref "R11") (pin "2") (pinfunction "2_2") (pintype "passive"))
      (node (ref "U2") (pin "1") (pinfunction "LINEOV_1") (pintype "input"))
    )
    (net (code "41") (name "Net-(U2-LINEUV)") (class "Default")
      (node (ref "R10") (pin "2") (pinfunction "2_2") (pintype "passive"))
      (node (ref "R6") (pin "1") (pinfunction "1_1") (pintype "passive"))
      (node (ref "R9") (pin "2") (pinfunction "2_2") (pintype "passive"))
      (node (ref "U2") (pin "15") (pinfunction "LINEUV_15") (pintype "input"))
    )
    (net (code "42") (name "Net-(U2-REF)") (class "Default")
      (node (ref "C13") (pin "2") (pinfunction "2_2") (pintype "passive"))
      (node (ref "U2") (pin "14") (pinfunction "REF_14") (pintype "output"))
    )
    (net (code "43") (name "Net-(U2-SLOPE)") (class "Default")
      (node (ref "C9") (pin "2") (pinfunction "2_2") (pintype "passive"))
      (node (ref "U2") (pin "5") (pinfunction "SLOPE_5") (pintype "passive"))
    )
    (net (code "44") (name "Net-(U2-SS)") (class "Default")
      (node (ref "R23") (pin "2") (pinfunction "2_2") (pintype "passive"))
      (node (ref "U2") (pin "7") (pinfunction "SS_7") (pintype "input"))
    )
    (net (code "45") (name "Net-(U3-CHG)") (class "Default")
      (node (ref "R36") (pin "2") (pinfunction "2_2") (pintype "passive"))
      (node (ref "U3") (pin "10") (pinfunction "CHG_10") (pintype "passive"))
    )
    (net (code "46") (name "Net-(U3-CS1)") (class "Default")
      (node (ref "C20") (pin "2") (pinfunction "2_2") (pintype "passive"))
      (node (ref "R39") (pin "2") (pinfunction "2_2") (pintype "passive"))
      (node (ref "U3") (pin "4") (pinfunction "CS1_4") (pintype "input"))
    )
    (net (code "47") (name "Net-(U3-CS2)") (class "Default")
      (node (ref "C22") (pin "2") (pinfunction "2_2") (pintype "passive"))
      (node (ref "R43") (pin "2") (pinfunction "2_2") (pintype "passive"))
      (node (ref "U3") (pin "6") (pinfunction "CS2_6") (pintype "input"))
    )
    (net (code "48") (name "Net-(U3-DISCHG)") (class "Default")
      (node (ref "R35") (pin "2") (pinfunction "2_2") (pintype "passive"))
      (node (ref "U3") (pin "9") (pinfunction "DISCHG_9") (pintype "passive"))
    )
    (net (code "49") (name "Net-(U3-LINEHYS)") (class "Default")
      (node (ref "R49") (pin "1") (pinfunction "1_1") (pintype "passive"))
      (node (ref "U3") (pin "2") (pinfunction "LINEHYS_2") (pintype "input"))
    )
    (net (code "50") (name "Net-(U3-LINEOV)") (class "Default")
      (node (ref "R47") (pin "2") (pinfunction "2_2") (pintype "passive"))
      (node (ref "R48") (pin "1") (pinfunction "1_1") (pintype "passive"))
      (node (ref "U3") (pin "1") (pinfunction "LINEOV_1") (pintype "input"))
    )
    (net (code "51") (name "Net-(U3-LINEUV)") (class "Default")
      (node (ref "R48") (pin "2") (pinfunction "2_2") (pintype "passive"))
      (node (ref "R49") (pin "2") (pinfunction "2_2") (pintype "passive"))
      (node (ref "R50") (pin "1") (pinfunction "1_1") (pintype "passive"))
      (node (ref "U3") (pin "15") (pinfunction "LINEUV_15") (pintype "input"))
    )
    (net (code "52") (name "Net-(U3-REF)") (class "Default")
      (node (ref "C16") (pin "2") (pinfunction "2_2") (pintype "passive"))
      (node (ref "U3") (pin "14") (pinfunction "REF_14") (pintype "output"))
    )
    (net (code "53") (name "Net-(U3-SLOPE)") (class "Default")
      (node (ref "C18") (pin "2") (pinfunction "2_2") (pintype "passive"))
      (node (ref "U3") (pin "5") (pinfunction "SLOPE_5") (pintype "passive"))
    )
    (net (code "54") (name "Net-(U3-SS)") (class "Default")
      (node (ref "R38") (pin "2") (pinfunction "2_2") (pintype "passive"))
      (node (ref "U3") (pin "7") (pinfunction "SS_7") (pintype "input"))
    )
  )
)
